# R121X.net
KiCad netlist of a schematic drawn in EAGLE
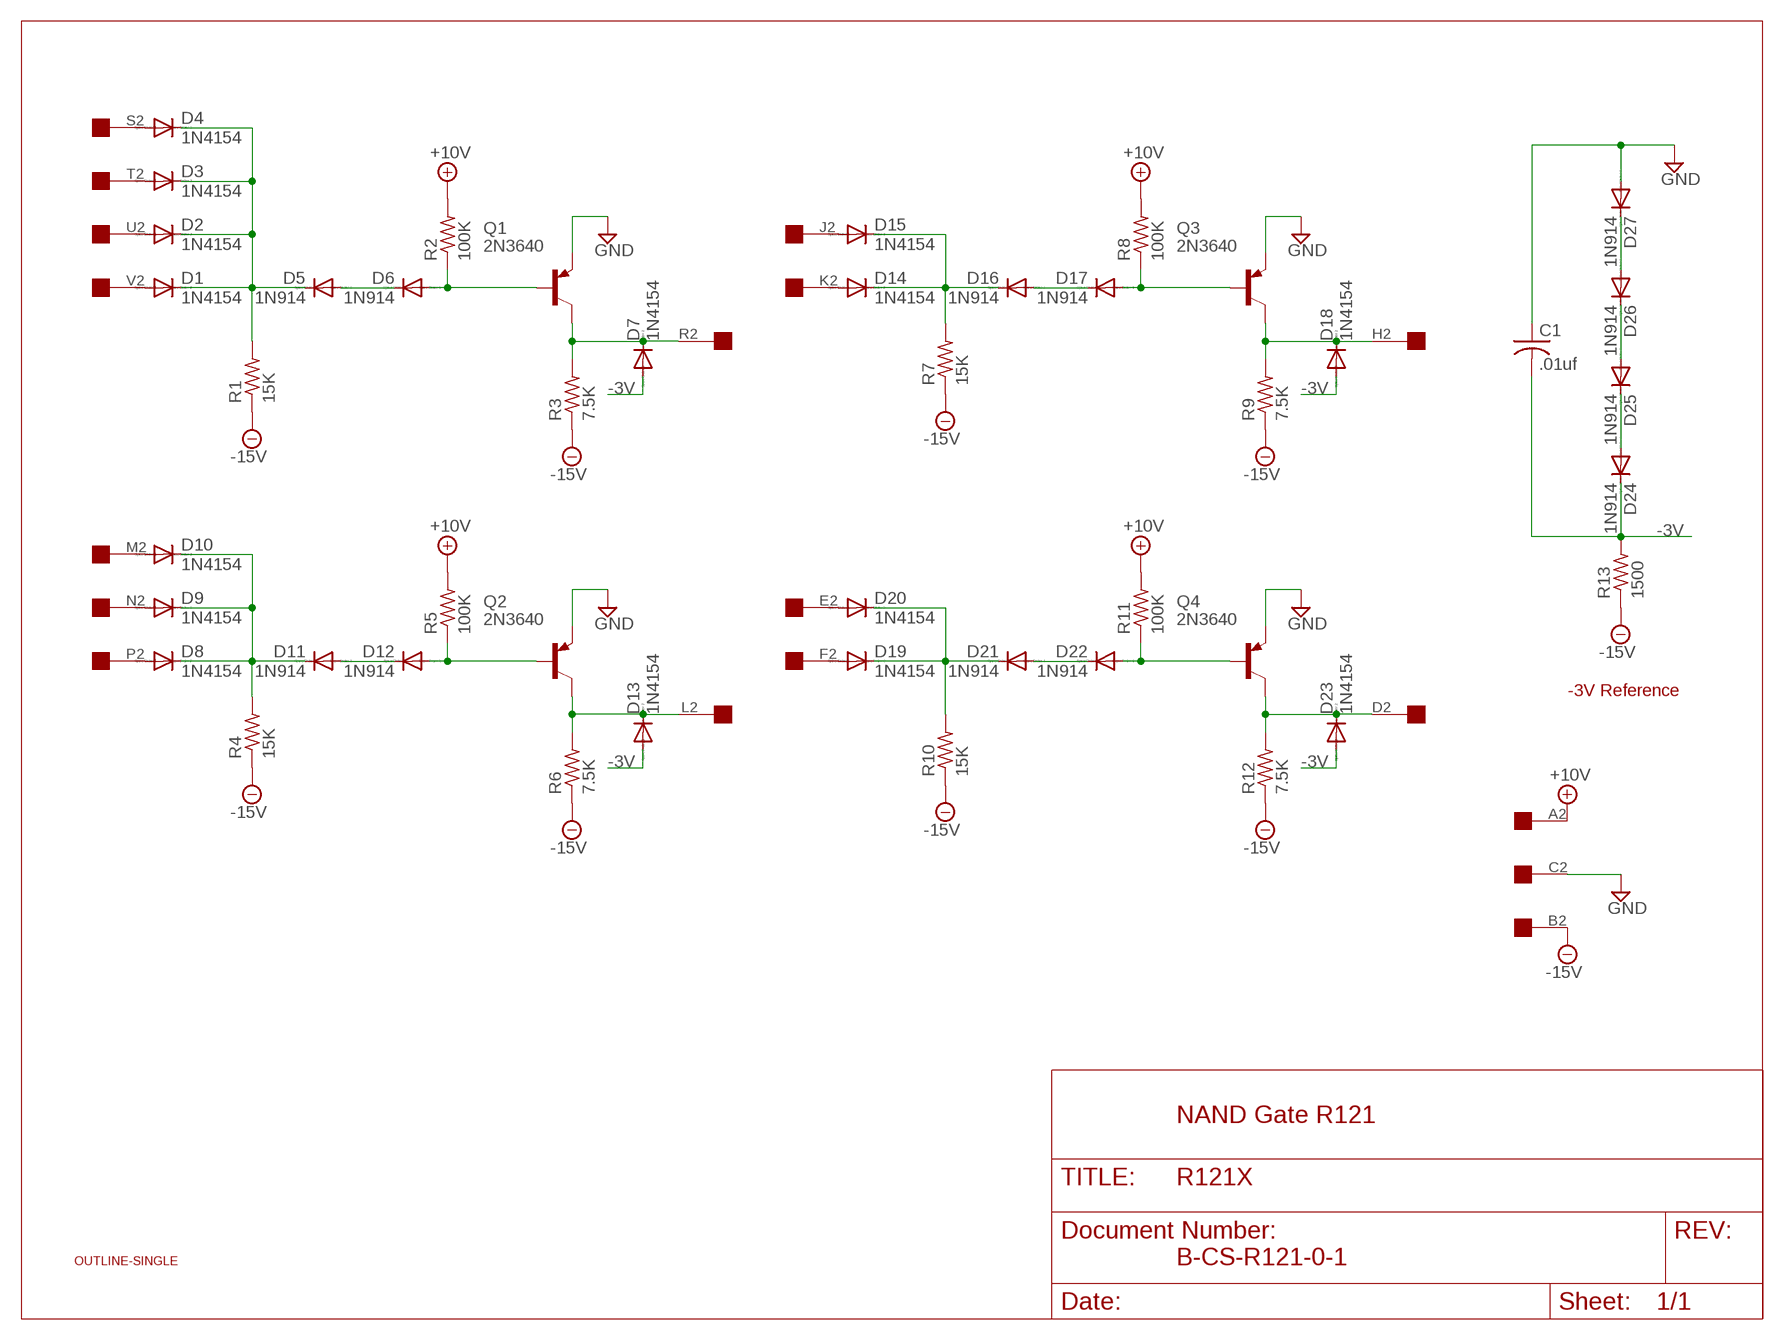
[diagram p0: schematic, sheet 1]

(export (version "E")
  (design (tool "Eeschema 10.0.6"))
  (components
    (comp (ref "C1")
      (value ".01uf")
      (footprint "eagle-import:C050-025X075")
      (libsource (lib "eagle-import") (part "C-US050-025X075"))
    )
    (comp (ref "D1")
      (value "1N4154")
      (footprint "eagle-import:DO35-10")
      (libsource (lib "eagle-import") (part "1N4148DO35-10"))
    )
    (comp (ref "D2")
      (value "1N4154")
      (footprint "eagle-import:DO35-10")
      (libsource (lib "eagle-import") (part "1N4148DO35-10"))
    )
    (comp (ref "D3")
      (value "1N4154")
      (footprint "eagle-import:DO35-10")
      (libsource (lib "eagle-import") (part "1N4148DO35-10"))
    )
    (comp (ref "D4")
      (value "1N4154")
      (footprint "eagle-import:DO35-10")
      (libsource (lib "eagle-import") (part "1N4148DO35-10"))
    )
    (comp (ref "D5")
      (value "1N914")
      (footprint "eagle-import:DO35-10")
      (libsource (lib "eagle-import") (part "1N4148DO35-10"))
    )
    (comp (ref "D6")
      (value "1N914")
      (footprint "eagle-import:DO35-10")
      (libsource (lib "eagle-import") (part "1N4148DO35-10"))
    )
    (comp (ref "D7")
      (value "1N4154")
      (footprint "eagle-import:DO35-10")
      (libsource (lib "eagle-import") (part "1N4148DO35-10"))
    )
    (comp (ref "D8")
      (value "1N4154")
      (footprint "eagle-import:DO35-10")
      (libsource (lib "eagle-import") (part "1N4148DO35-10"))
    )
    (comp (ref "D9")
      (value "1N4154")
      (footprint "eagle-import:DO35-10")
      (libsource (lib "eagle-import") (part "1N4148DO35-10"))
    )
    (comp (ref "D10")
      (value "1N4154")
      (footprint "eagle-import:DO35-10")
      (libsource (lib "eagle-import") (part "1N4148DO35-10"))
    )
    (comp (ref "D11")
      (value "1N914")
      (footprint "eagle-import:DO35-10")
      (libsource (lib "eagle-import") (part "1N4148DO35-10"))
    )
    (comp (ref "D12")
      (value "1N914")
      (footprint "eagle-import:DO35-10")
      (libsource (lib "eagle-import") (part "1N4148DO35-10"))
    )
    (comp (ref "D13")
      (value "1N4154")
      (footprint "eagle-import:DO35-10")
      (libsource (lib "eagle-import") (part "1N4148DO35-10"))
    )
    (comp (ref "D14")
      (value "1N4154")
      (footprint "eagle-import:DO35-10")
      (libsource (lib "eagle-import") (part "1N4148DO35-10"))
    )
    (comp (ref "D15")
      (value "1N4154")
      (footprint "eagle-import:DO35-10")
      (libsource (lib "eagle-import") (part "1N4148DO35-10"))
    )
    (comp (ref "D16")
      (value "1N914")
      (footprint "eagle-import:DO35-10")
      (libsource (lib "eagle-import") (part "1N4148DO35-10"))
    )
    (comp (ref "D17")
      (value "1N914")
      (footprint "eagle-import:DO35-10")
      (libsource (lib "eagle-import") (part "1N4148DO35-10"))
    )
    (comp (ref "D18")
      (value "1N4154")
      (footprint "eagle-import:DO35-10")
      (libsource (lib "eagle-import") (part "1N4148DO35-10"))
    )
    (comp (ref "D19")
      (value "1N4154")
      (footprint "eagle-import:DO35-10")
      (libsource (lib "eagle-import") (part "1N4148DO35-10"))
    )
    (comp (ref "D20")
      (value "1N4154")
      (footprint "eagle-import:DO35-10")
      (libsource (lib "eagle-import") (part "1N4148DO35-10"))
    )
    (comp (ref "D21")
      (value "1N914")
      (footprint "eagle-import:DO35-10")
      (libsource (lib "eagle-import") (part "1N4148DO35-10"))
    )
    (comp (ref "D22")
      (value "1N914")
      (footprint "eagle-import:DO35-10")
      (libsource (lib "eagle-import") (part "1N4148DO35-10"))
    )
    (comp (ref "D23")
      (value "1N4154")
      (footprint "eagle-import:DO35-10")
      (libsource (lib "eagle-import") (part "1N4148DO35-10"))
    )
    (comp (ref "D24")
      (value "1N914")
      (footprint "eagle-import:DO35-10")
      (libsource (lib "eagle-import") (part "1N4148DO35-10"))
    )
    (comp (ref "D25")
      (value "1N914")
      (footprint "eagle-import:DO35-10")
      (libsource (lib "eagle-import") (part "1N4148DO35-10"))
    )
    (comp (ref "D26")
      (value "1N914")
      (footprint "eagle-import:DO35-10")
      (libsource (lib "eagle-import") (part "1N4148DO35-10"))
    )
    (comp (ref "D27")
      (value "1N914")
      (footprint "eagle-import:DO35-10")
      (libsource (lib "eagle-import") (part "1N4148DO35-10"))
    )
    (comp (ref "Q1")
      (value "2N3640")
      (footprint "eagle-import:TO39")
      (libsource (lib "eagle-import") (part "2N3637"))
    )
    (comp (ref "Q2")
      (value "2N3640")
      (footprint "eagle-import:TO39")
      (libsource (lib "eagle-import") (part "2N3637"))
    )
    (comp (ref "Q3")
      (value "2N3640")
      (footprint "eagle-import:TO39")
      (libsource (lib "eagle-import") (part "2N3637"))
    )
    (comp (ref "Q4")
      (value "2N3640")
      (footprint "eagle-import:TO39")
      (libsource (lib "eagle-import") (part "2N3637"))
    )
    (comp (ref "R1")
      (value "15K")
      (footprint "eagle-import:0207_10")
      (libsource (lib "eagle-import") (part "R-US_0207/10"))
    )
    (comp (ref "R2")
      (value "100K")
      (footprint "eagle-import:0207_10")
      (libsource (lib "eagle-import") (part "R-US_0207/10"))
    )
    (comp (ref "R3")
      (value "7.5K")
      (footprint "eagle-import:0207_10")
      (libsource (lib "eagle-import") (part "R-US_0207/10"))
    )
    (comp (ref "R4")
      (value "15K")
      (footprint "eagle-import:0207_10")
      (libsource (lib "eagle-import") (part "R-US_0207/10"))
    )
    (comp (ref "R5")
      (value "100K")
      (footprint "eagle-import:0207_10")
      (libsource (lib "eagle-import") (part "R-US_0207/10"))
    )
    (comp (ref "R6")
      (value "7.5K")
      (footprint "eagle-import:0207_10")
      (libsource (lib "eagle-import") (part "R-US_0207/10"))
    )
    (comp (ref "R7")
      (value "15K")
      (footprint "eagle-import:0207_10")
      (libsource (lib "eagle-import") (part "R-US_0207/10"))
    )
    (comp (ref "R8")
      (value "100K")
      (footprint "eagle-import:0207_10")
      (libsource (lib "eagle-import") (part "R-US_0207/10"))
    )
    (comp (ref "R9")
      (value "7.5K")
      (footprint "eagle-import:0207_10")
      (libsource (lib "eagle-import") (part "R-US_0207/10"))
    )
    (comp (ref "R10")
      (value "15K")
      (footprint "eagle-import:0207_10")
      (libsource (lib "eagle-import") (part "R-US_0207/10"))
    )
    (comp (ref "R11")
      (value "100K")
      (footprint "eagle-import:0207_10")
      (libsource (lib "eagle-import") (part "R-US_0207/10"))
    )
    (comp (ref "R12")
      (value "7.5K")
      (footprint "eagle-import:0207_10")
      (libsource (lib "eagle-import") (part "R-US_0207/10"))
    )
    (comp (ref "R13")
      (value "1500")
      (footprint "eagle-import:0207_10")
      (libsource (lib "eagle-import") (part "R-US_0207/10"))
    )
    (comp (ref "U$1")
      (value "OUTLINE-SINGLE")
      (footprint "eagle-import:SINGLE")
      (libsource (lib "eagle-import") (part "OUTLINE-SINGLE"))
    )
    (comp (ref "U$2")
      (value "EDGE-1")
      (footprint "eagle-import:EDGE-CON1")
      (libsource (lib "eagle-import") (part "EDGE-1"))
    )
  )
  (nets
    (net (code "1") (name "+10V") (class "Default")
      (node (ref "R11") (pin "2") (pinfunction "2_2") (pintype "passive"))
      (node (ref "R2") (pin "2") (pinfunction "2_2") (pintype "passive"))
      (node (ref "R5") (pin "2") (pinfunction "2_2") (pintype "passive"))
      (node (ref "R8") (pin "2") (pinfunction "2_2") (pintype "passive"))
      (node (ref "U$2") (pin "A2") (pinfunction "1_A2") (pintype "bidirectional"))
    )
    (net (code "2") (name "-15V") (class "Default")
      (node (ref "R1") (pin "1") (pinfunction "1_1") (pintype "passive"))
      (node (ref "R10") (pin "1") (pinfunction "1_1") (pintype "passive"))
      (node (ref "R12") (pin "1") (pinfunction "1_1") (pintype "passive"))
      (node (ref "R13") (pin "1") (pinfunction "1_1") (pintype "passive"))
      (node (ref "R3") (pin "1") (pinfunction "1_1") (pintype "passive"))
      (node (ref "R4") (pin "1") (pinfunction "1_1") (pintype "passive"))
      (node (ref "R6") (pin "1") (pinfunction "1_1") (pintype "passive"))
      (node (ref "R7") (pin "1") (pinfunction "1_1") (pintype "passive"))
      (node (ref "R9") (pin "1") (pinfunction "1_1") (pintype "passive"))
      (node (ref "U$2") (pin "B2") (pinfunction "1_B2") (pintype "bidirectional"))
    )
    (net (code "3") (name "/-3V") (class "Default")
      (node (ref "C1") (pin "2") (pinfunction "2_2") (pintype "passive"))
      (node (ref "D13") (pin "A") (pinfunction "A_A") (pintype "passive"))
      (node (ref "D18") (pin "A") (pinfunction "A_A") (pintype "passive"))
      (node (ref "D23") (pin "A") (pinfunction "A_A") (pintype "passive"))
      (node (ref "D24") (pin "C") (pinfunction "C_C") (pintype "passive"))
      (node (ref "D7") (pin "A") (pinfunction "A_A") (pintype "passive"))
      (node (ref "R13") (pin "2") (pinfunction "2_2") (pintype "passive"))
    )
    (net (code "4") (name "GND") (class "Default")
      (node (ref "C1") (pin "1") (pinfunction "1_1") (pintype "passive"))
      (node (ref "D27") (pin "A") (pinfunction "A_A") (pintype "passive"))
      (node (ref "Q1") (pin "1") (pinfunction "E_1") (pintype "passive"))
      (node (ref "Q2") (pin "1") (pinfunction "E_1") (pintype "passive"))
      (node (ref "Q3") (pin "1") (pinfunction "E_1") (pintype "passive"))
      (node (ref "Q4") (pin "1") (pinfunction "E_1") (pintype "passive"))
      (node (ref "U$2") (pin "C2") (pinfunction "1_C2") (pintype "bidirectional"))
    )
    (net (code "5") (name "Net-(D1-PadC)") (class "Default")
      (node (ref "D1") (pin "C") (pinfunction "C_C") (pintype "passive"))
      (node (ref "D2") (pin "C") (pinfunction "C_C") (pintype "passive"))
      (node (ref "D3") (pin "C") (pinfunction "C_C") (pintype "passive"))
      (node (ref "D4") (pin "C") (pinfunction "C_C") (pintype "passive"))
      (node (ref "D5") (pin "C") (pinfunction "C_C") (pintype "passive"))
      (node (ref "R1") (pin "2") (pinfunction "2_2") (pintype "passive"))
    )
    (net (code "6") (name "Net-(D5-PadA)") (class "Default")
      (node (ref "D5") (pin "A") (pinfunction "A_A") (pintype "passive"))
      (node (ref "D6") (pin "C") (pinfunction "C_C") (pintype "passive"))
    )
    (net (code "7") (name "Net-(D10-PadC)") (class "Default")
      (node (ref "D10") (pin "C") (pinfunction "C_C") (pintype "passive"))
      (node (ref "D11") (pin "C") (pinfunction "C_C") (pintype "passive"))
      (node (ref "D8") (pin "C") (pinfunction "C_C") (pintype "passive"))
      (node (ref "D9") (pin "C") (pinfunction "C_C") (pintype "passive"))
      (node (ref "R4") (pin "2") (pinfunction "2_2") (pintype "passive"))
    )
    (net (code "8") (name "Net-(D11-PadA)") (class "Default")
      (node (ref "D11") (pin "A") (pinfunction "A_A") (pintype "passive"))
      (node (ref "D12") (pin "C") (pinfunction "C_C") (pintype "passive"))
    )
    (net (code "9") (name "Net-(D14-PadC)") (class "Default")
      (node (ref "D14") (pin "C") (pinfunction "C_C") (pintype "passive"))
      (node (ref "D15") (pin "C") (pinfunction "C_C") (pintype "passive"))
      (node (ref "D16") (pin "C") (pinfunction "C_C") (pintype "passive"))
      (node (ref "R7") (pin "2") (pinfunction "2_2") (pintype "passive"))
    )
    (net (code "10") (name "Net-(D16-PadA)") (class "Default")
      (node (ref "D16") (pin "A") (pinfunction "A_A") (pintype "passive"))
      (node (ref "D17") (pin "C") (pinfunction "C_C") (pintype "passive"))
    )
    (net (code "11") (name "Net-(D19-PadC)") (class "Default")
      (node (ref "D19") (pin "C") (pinfunction "C_C") (pintype "passive"))
      (node (ref "D20") (pin "C") (pinfunction "C_C") (pintype "passive"))
      (node (ref "D21") (pin "C") (pinfunction "C_C") (pintype "passive"))
      (node (ref "R10") (pin "2") (pinfunction "2_2") (pintype "passive"))
    )
    (net (code "12") (name "Net-(D21-PadA)") (class "Default")
      (node (ref "D21") (pin "A") (pinfunction "A_A") (pintype "passive"))
      (node (ref "D22") (pin "C") (pinfunction "C_C") (pintype "passive"))
    )
    (net (code "13") (name "Net-(D24-PadA)") (class "Default")
      (node (ref "D24") (pin "A") (pinfunction "A_A") (pintype "passive"))
      (node (ref "D25") (pin "C") (pinfunction "C_C") (pintype "passive"))
    )
    (net (code "14") (name "Net-(D25-PadA)") (class "Default")
      (node (ref "D25") (pin "A") (pinfunction "A_A") (pintype "passive"))
      (node (ref "D26") (pin "C") (pinfunction "C_C") (pintype "passive"))
    )
    (net (code "15") (name "Net-(D26-PadA)") (class "Default")
      (node (ref "D26") (pin "A") (pinfunction "A_A") (pintype "passive"))
      (node (ref "D27") (pin "C") (pinfunction "C_C") (pintype "passive"))
    )
    (net (code "16") (name "Net-(Q1-B)") (class "Default")
      (node (ref "D6") (pin "A") (pinfunction "A_A") (pintype "passive"))
      (node (ref "Q1") (pin "2") (pinfunction "B_2") (pintype "passive"))
      (node (ref "R2") (pin "1") (pinfunction "1_1") (pintype "passive"))
    )
    (net (code "17") (name "Net-(Q1-C)") (class "Default")
      (node (ref "D7") (pin "C") (pinfunction "C_C") (pintype "passive"))
      (node (ref "Q1") (pin "3") (pinfunction "C_3") (pintype "passive"))
      (node (ref "R3") (pin "2") (pinfunction "2_2") (pintype "passive"))
      (node (ref "U$2") (pin "R2") (pinfunction "1_R2") (pintype "bidirectional"))
    )
    (net (code "18") (name "Net-(Q2-B)") (class "Default")
      (node (ref "D12") (pin "A") (pinfunction "A_A") (pintype "passive"))
      (node (ref "Q2") (pin "2") (pinfunction "B_2") (pintype "passive"))
      (node (ref "R5") (pin "1") (pinfunction "1_1") (pintype "passive"))
    )
    (net (code "19") (name "Net-(Q2-C)") (class "Default")
      (node (ref "D13") (pin "C") (pinfunction "C_C") (pintype "passive"))
      (node (ref "Q2") (pin "3") (pinfunction "C_3") (pintype "passive"))
      (node (ref "R6") (pin "2") (pinfunction "2_2") (pintype "passive"))
      (node (ref "U$2") (pin "L2") (pinfunction "1_L2") (pintype "bidirectional"))
    )
    (net (code "20") (name "Net-(Q3-B)") (class "Default")
      (node (ref "D17") (pin "A") (pinfunction "A_A") (pintype "passive"))
      (node (ref "Q3") (pin "2") (pinfunction "B_2") (pintype "passive"))
      (node (ref "R8") (pin "1") (pinfunction "1_1") (pintype "passive"))
    )
    (net (code "21") (name "Net-(Q3-C)") (class "Default")
      (node (ref "D18") (pin "C") (pinfunction "C_C") (pintype "passive"))
      (node (ref "Q3") (pin "3") (pinfunction "C_3") (pintype "passive"))
      (node (ref "R9") (pin "2") (pinfunction "2_2") (pintype "passive"))
      (node (ref "U$2") (pin "H2") (pinfunction "1_H2") (pintype "bidirectional"))
    )
    (net (code "22") (name "Net-(Q4-B)") (class "Default")
      (node (ref "D22") (pin "A") (pinfunction "A_A") (pintype "passive"))
      (node (ref "Q4") (pin "2") (pinfunction "B_2") (pintype "passive"))
      (node (ref "R11") (pin "1") (pinfunction "1_1") (pintype "passive"))
    )
    (net (code "23") (name "Net-(Q4-C)") (class "Default")
      (node (ref "D23") (pin "C") (pinfunction "C_C") (pintype "passive"))
      (node (ref "Q4") (pin "3") (pinfunction "C_3") (pintype "passive"))
      (node (ref "R12") (pin "2") (pinfunction "2_2") (pintype "passive"))
      (node (ref "U$2") (pin "D2") (pinfunction "1_D2") (pintype "bidirectional"))
    )
    (net (code "24") (name "Net-(U$2E-1)") (class "Default")
      (node (ref "D20") (pin "A") (pinfunction "A_A") (pintype "passive"))
      (node (ref "U$2") (pin "E2") (pinfunction "1_E2") (pintype "bidirectional"))
    )
    (net (code "25") (name "Net-(U$2F-1)") (class "Default")
      (node (ref "D19") (pin "A") (pinfunction "A_A") (pintype "passive"))
      (node (ref "U$2") (pin "F2") (pinfunction "1_F2") (pintype "bidirectional"))
    )
    (net (code "26") (name "Net-(U$2H-1)") (class "Default")
      (node (ref "D15") (pin "A") (pinfunction "A_A") (pintype "passive"))
      (node (ref "U$2") (pin "J2") (pinfunction "1_J2") (pintype "bidirectional"))
    )
    (net (code "27") (name "Net-(U$2I-1)") (class "Default")
      (node (ref "D14") (pin "A") (pinfunction "A_A") (pintype "passive"))
      (node (ref "U$2") (pin "K2") (pinfunction "1_K2") (pintype "bidirectional"))
    )
    (net (code "28") (name "Net-(U$2K-1)") (class "Default")
      (node (ref "D10") (pin "A") (pinfunction "A_A") (pintype "passive"))
      (node (ref "U$2") (pin "M2") (pinfunction "1_M2") (pintype "bidirectional"))
    )
    (net (code "29") (name "Net-(U$2L-1)") (class "Default")
      (node (ref "D9") (pin "A") (pinfunction "A_A") (pintype "passive"))
      (node (ref "U$2") (pin "N2") (pinfunction "1_N2") (pintype "bidirectional"))
    )
    (net (code "30") (name "Net-(U$2M-1)") (class "Default")
      (node (ref "D8") (pin "A") (pinfunction "A_A") (pintype "passive"))
      (node (ref "U$2") (pin "P2") (pinfunction "1_P2") (pintype "bidirectional"))
    )
    (net (code "31") (name "Net-(U$2O-1)") (class "Default")
      (node (ref "D4") (pin "A") (pinfunction "A_A") (pintype "passive"))
      (node (ref "U$2") (pin "S2") (pinfunction "1_S2") (pintype "bidirectional"))
    )
    (net (code "32") (name "Net-(U$2P-1)") (class "Default")
      (node (ref "D3") (pin "A") (pinfunction "A_A") (pintype "passive"))
      (node (ref "U$2") (pin "T2") (pinfunction "1_T2") (pintype "bidirectional"))
    )
    (net (code "33") (name "Net-(U$2Q-1)") (class "Default")
      (node (ref "D2") (pin "A") (pinfunction "A_A") (pintype "passive"))
      (node (ref "U$2") (pin "U2") (pinfunction "1_U2") (pintype "bidirectional"))
    )
    (net (code "34") (name "Net-(U$2R-1)") (class "Default")
      (node (ref "D1") (pin "A") (pinfunction "A_A") (pintype "passive"))
      (node (ref "U$2") (pin "V2") (pinfunction "1_V2") (pintype "bidirectional"))
    )
  )
)
